# attiniest85-power-shield-mk-1_0.net
KiCad netlist of a schematic drawn in EAGLE
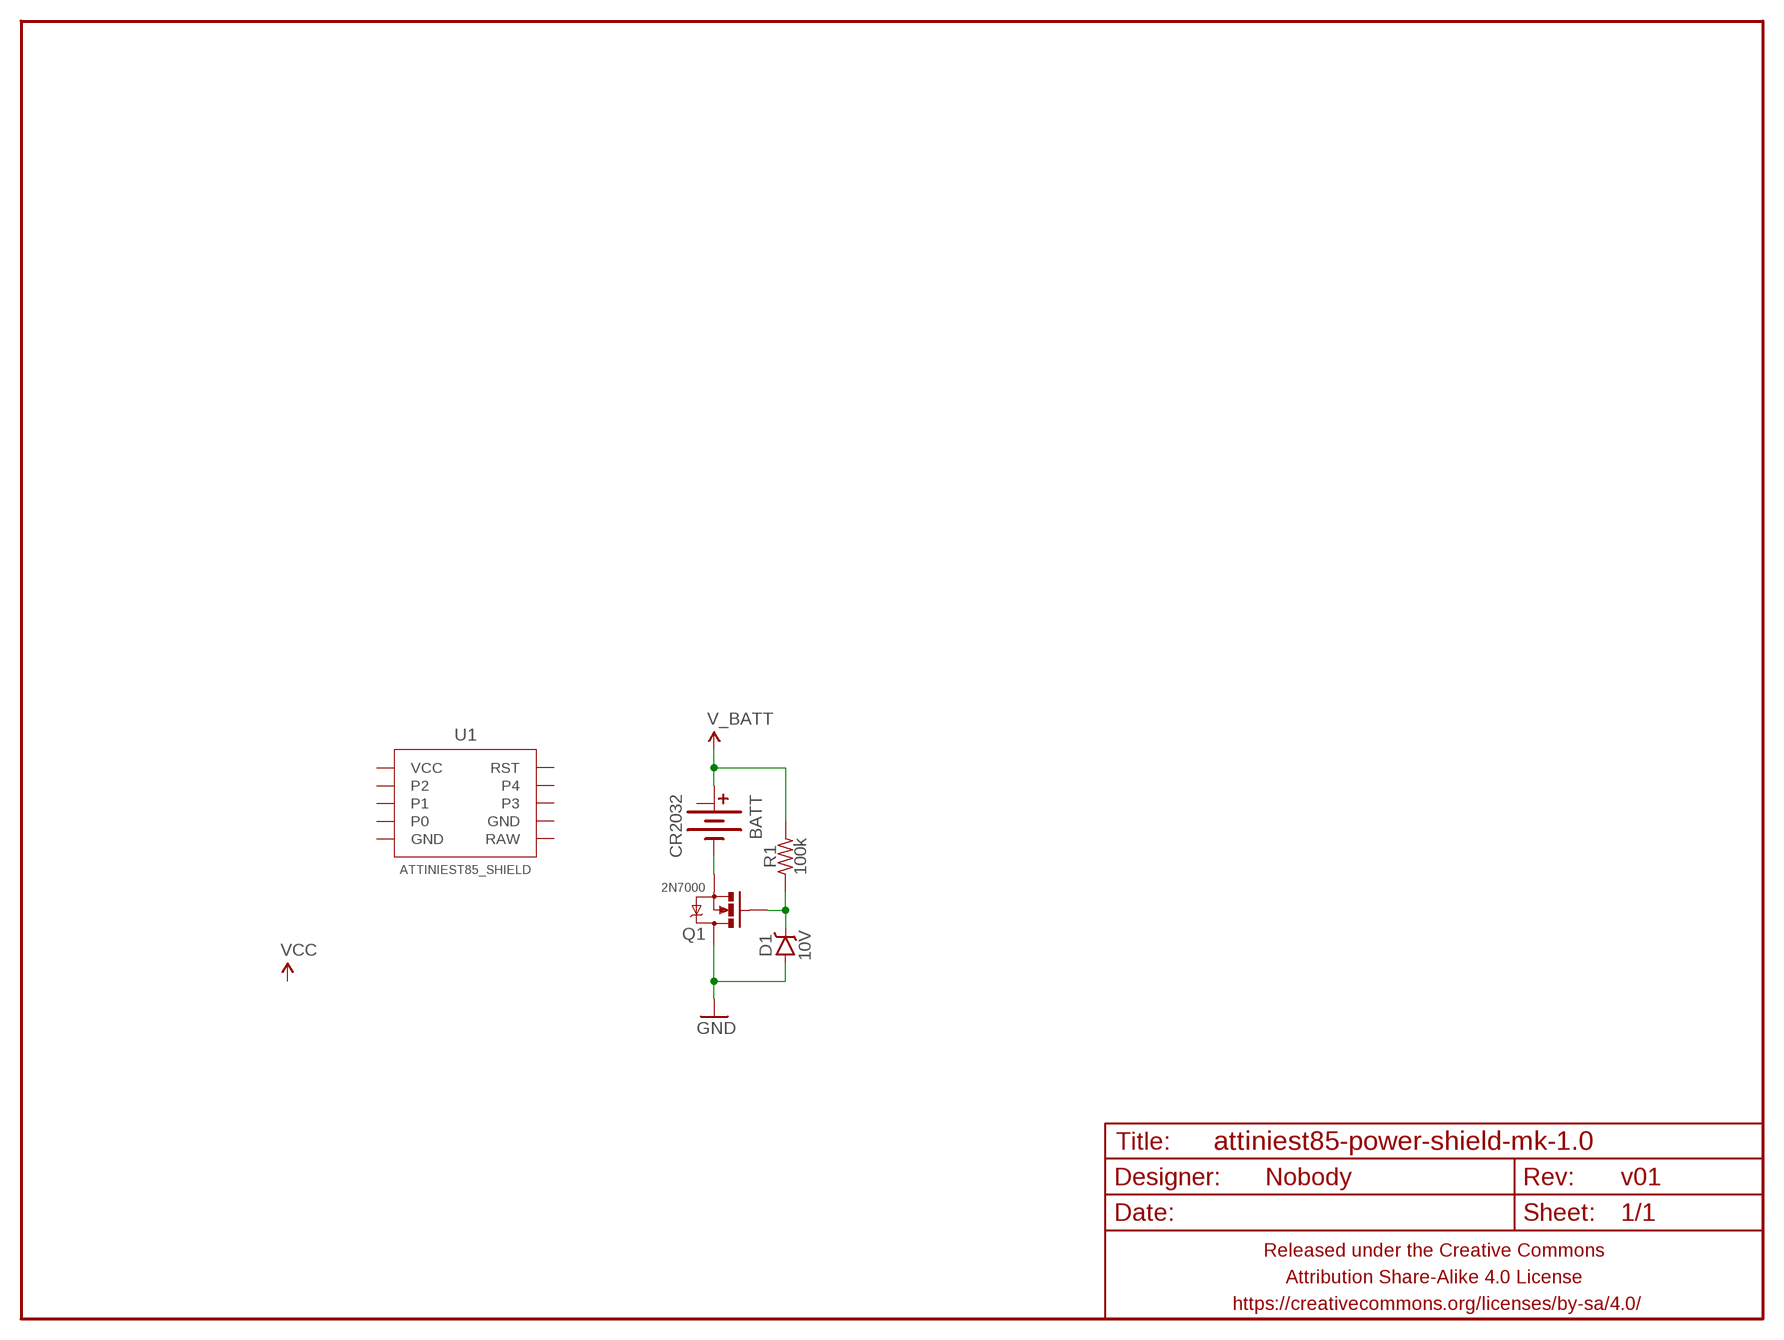
[diagram p0: schematic, sheet 1]

(export (version "E")
  (design (tool "Eeschema 10.0.6"))
  (components
    (comp (ref "BATT")
      (value "CR2032")
      (footprint "eagle-import:BATTCON_20MM_MINE")
      (libsource (lib "eagle-import") (part "BATTERY-COINCR2032_SMD"))
    )
    (comp (ref "D1")
      (value "10V")
      (footprint "eagle-import:DIODE-ZENNER-7.62MM")
      (libsource (lib "eagle-import") (part "DIODE-ZENER7.62MM-PTH"))
    )
    (comp (ref "FRAME1")
      (value "FRAME-LETTERNO_PACKAGE")
      (footprint "eagle-import:DUMMY")
      (fields (field (name "DESIGNER") "Nobody"))
      (libsource (lib "eagle-import") (part "FRAME-LETTERNO_PACKAGE"))
    )
    (comp (ref "Q1")
      (value "2N7000")
      (footprint "eagle-import:TO-92-AMMO")
      (libsource (lib "eagle-import") (part "MOSFET-NCHANNEL2N7000-AMMO"))
    )
    (comp (ref "R1")
      (value "100k")
      (footprint "eagle-import:RESISTOR-AXIAL-PTH-7.62MM")
      (libsource (lib "eagle-import") (part "RESISTORPTH-AXIAL-7.62MM"))
    )
    (comp (ref "U1")
      (value "ATTINIEST85_SHIELD")
      (footprint "eagle-import:ATTINIEST85_SHIELD")
      (libsource (lib "eagle-import") (part "ATTINIEST85_SHIELD"))
    )
  )
  (nets
    (net (code "1") (name "GND") (class "Default")
      (node (ref "D1") (pin "A") (pinfunction "A_A") (pintype "passive"))
      (node (ref "Q1") (pin "3") (pinfunction "D_3") (pintype "passive"))
    )
    (net (code "2") (name "Net-(BATT--)") (class "Default")
      (node (ref "BATT") (pin "BOTTOM") (pinfunction "-_BOTTOM") (pintype "bidirectional"))
      (node (ref "Q1") (pin "1") (pinfunction "S_1") (pintype "passive"))
    )
    (net (code "3") (name "Net-(D1-C)") (class "Default")
      (node (ref "D1") (pin "K") (pinfunction "C_K") (pintype "passive"))
      (node (ref "Q1") (pin "2") (pinfunction "G_2") (pintype "passive"))
      (node (ref "R1") (pin "P$1") (pinfunction "1_P$1") (pintype "passive"))
    )
    (net (code "5") (name "V_BATT") (class "Default")
      (node (ref "BATT") (pin "TOP@1") (pinfunction "+_TOP@1") (pintype "bidirectional"))
      (node (ref "R1") (pin "P$2") (pinfunction "2_P$2") (pintype "passive"))
    )
    (net (code "6") (name "unconnected-(BATT-+1-PadTOP@2)") (class "Default")
      (node (ref "BATT") (pin "TOP@2") (pinfunction "+1_TOP@2") (pintype "bidirectional"))
    )
    (net (code "7") (name "unconnected-(U1-GND-PadGND@1)") (class "Default")
      (node (ref "U1") (pin "GND@1") (pinfunction "GND_GND@1") (pintype "bidirectional"))
    )
    (net (code "8") (name "unconnected-(U1-GND-PadGND@2)") (class "Default")
      (node (ref "U1") (pin "GND@2") (pinfunction "GND_GND@2") (pintype "bidirectional"))
    )
    (net (code "9") (name "unconnected-(U1-P0-Pad0)") (class "Default")
      (node (ref "U1") (pin "0") (pinfunction "P0_0") (pintype "bidirectional"))
    )
    (net (code "10") (name "unconnected-(U1-P1-Pad1)") (class "Default")
      (node (ref "U1") (pin "1") (pinfunction "P1_1") (pintype "bidirectional"))
    )
    (net (code "11") (name "unconnected-(U1-P2-Pad2)") (class "Default")
      (node (ref "U1") (pin "2") (pinfunction "P2_2") (pintype "bidirectional"))
    )
    (net (code "12") (name "unconnected-(U1-P3-Pad3)") (class "Default")
      (node (ref "U1") (pin "3") (pinfunction "P3_3") (pintype "bidirectional"))
    )
    (net (code "13") (name "unconnected-(U1-P4-Pad4)") (class "Default")
      (node (ref "U1") (pin "4") (pinfunction "P4_4") (pintype "bidirectional"))
    )
    (net (code "14") (name "unconnected-(U1-PadRAW)") (class "Default")
      (node (ref "U1") (pin "RAW") (pinfunction "RAW_RAW") (pintype "bidirectional"))
    )
    (net (code "15") (name "unconnected-(U1-PadRST)") (class "Default")
      (node (ref "U1") (pin "RST") (pinfunction "RST_RST") (pintype "bidirectional"))
    )
    (net (code "16") (name "unconnected-(U1-PadVCC)") (class "Default")
      (node (ref "U1") (pin "VCC") (pinfunction "VCC_VCC") (pintype "bidirectional"))
    )
  )
)
